# ESPCAT.net
KiCad netlist of a schematic drawn in EAGLE
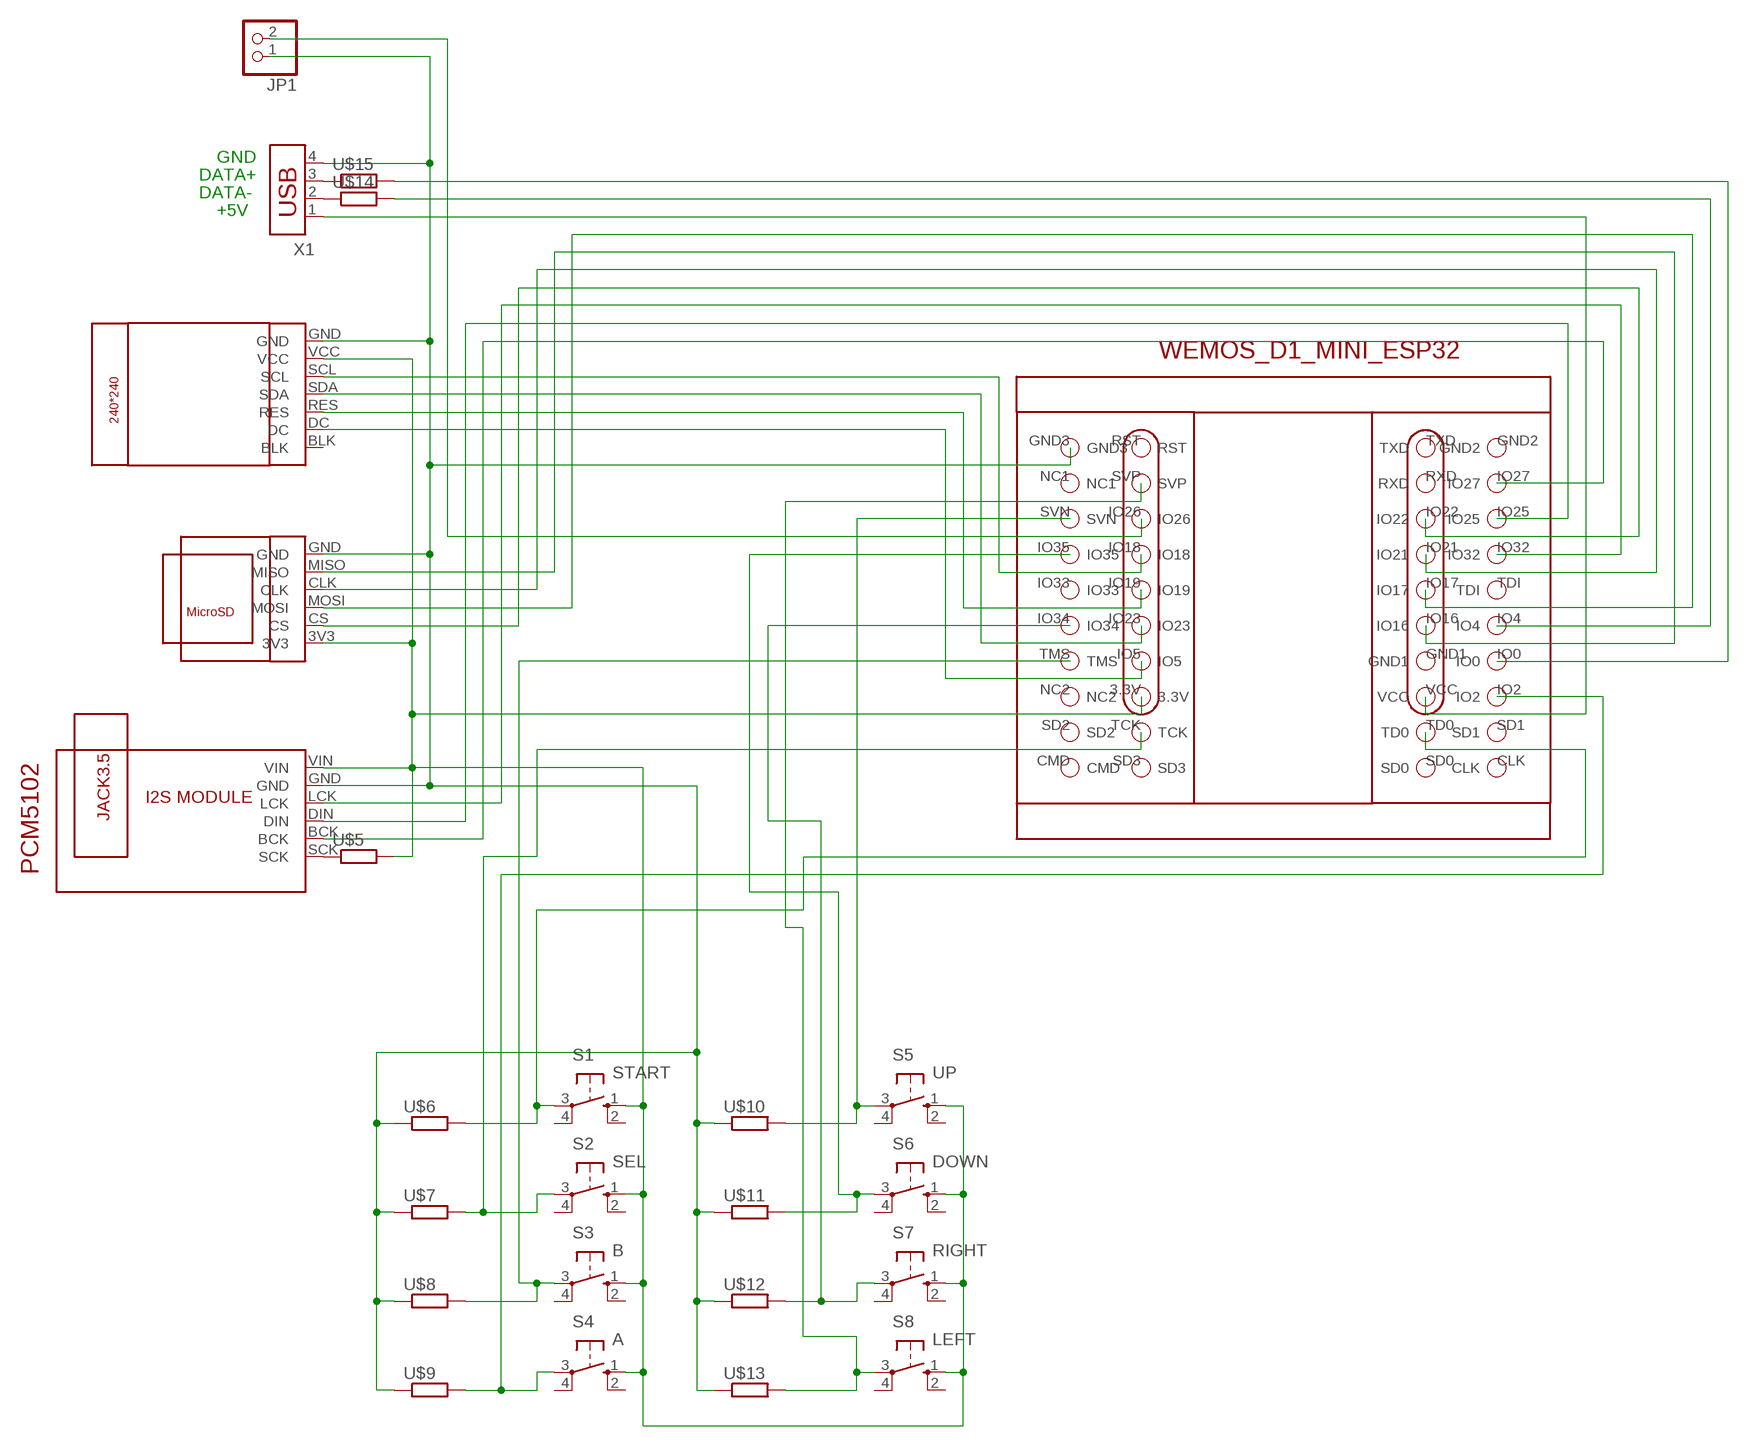
[diagram p0: schematic, sheet 1]

(export (version "E")
  (design (tool "Eeschema 10.0.6"))
  (components
    (comp (ref "JP1")
      (value "PINHD-1X2/90")
      (footprint "eagle-import:1X02_90")
      (libsource (lib "eagle-import") (part "PINHD-1X2/90"))
    )
    (comp (ref "S1")
      (value "START")
      (footprint "eagle-import:B3F-10XX")
      (fields (field (name "MPN") "B3F-1000"))
      (libsource (lib "eagle-import") (part "10-XX"))
    )
    (comp (ref "S2")
      (value "SEL")
      (footprint "eagle-import:B3F-10XX")
      (fields (field (name "MPN") "B3F-1000"))
      (libsource (lib "eagle-import") (part "10-XX"))
    )
    (comp (ref "S3")
      (value "B")
      (footprint "eagle-import:B3F-10XX")
      (fields (field (name "MPN") "B3F-1000"))
      (libsource (lib "eagle-import") (part "10-XX"))
    )
    (comp (ref "S4")
      (value "A")
      (footprint "eagle-import:B3F-10XX")
      (fields (field (name "MPN") "B3F-1000"))
      (libsource (lib "eagle-import") (part "10-XX"))
    )
    (comp (ref "S5")
      (value "UP")
      (footprint "eagle-import:B3F-10XX")
      (fields (field (name "MPN") "B3F-1000"))
      (libsource (lib "eagle-import") (part "10-XX"))
    )
    (comp (ref "S6")
      (value "DOWN")
      (footprint "eagle-import:B3F-10XX")
      (fields (field (name "MPN") "B3F-1000"))
      (libsource (lib "eagle-import") (part "10-XX"))
    )
    (comp (ref "S7")
      (value "RIGHT")
      (footprint "eagle-import:B3F-10XX")
      (fields (field (name "MPN") "B3F-1000"))
      (libsource (lib "eagle-import") (part "10-XX"))
    )
    (comp (ref "S8")
      (value "LEFT")
      (footprint "eagle-import:B3F-10XX")
      (fields (field (name "MPN") "B3F-1000"))
      (libsource (lib "eagle-import") (part "10-XX"))
    )
    (comp (ref "U$1")
      (value "WEMOS_D1_MINI_ESP32")
      (footprint "eagle-import:WEMOS_D1_MINI_ESP32")
      (libsource (lib "eagle-import") (part "WEMOS_D1_MINI_ESP32"))
    )
    (comp (ref "U$2")
      (value "ST7789-1.3INCH")
      (footprint "eagle-import:ST7789-1.3INCH")
      (libsource (lib "eagle-import") (part "ST7789-1.3INCH"))
    )
    (comp (ref "U$3")
      (value "MICROSD-CARD-MODULE")
      (footprint "eagle-import:MICROSD-CARD-MODULE")
      (libsource (lib "eagle-import") (part "MICROSD-CARD-MODULE"))
    )
    (comp (ref "U$4")
      (value "I2S-MODULE-PCM5102A-LITE")
      (footprint "eagle-import:I2S-MODULE-PCM5102A-LITE")
      (libsource (lib "eagle-import") (part "I2S-MODULE-PCM5102A-LITE"))
    )
    (comp (ref "U$5")
      (value "R-RESISTORR-0207/10H")
      (footprint "eagle-import:R-0207_10H")
      (libsource (lib "eagle-import") (part "R-RESISTORR-0207/10H"))
    )
    (comp (ref "U$6")
      (value "R-RESISTORR-0207/10H")
      (footprint "eagle-import:R-0207_10H")
      (libsource (lib "eagle-import") (part "R-RESISTORR-0207/10H"))
    )
    (comp (ref "U$7")
      (value "R-RESISTORR-0207/10H")
      (footprint "eagle-import:R-0207_10H")
      (libsource (lib "eagle-import") (part "R-RESISTORR-0207/10H"))
    )
    (comp (ref "U$8")
      (value "R-RESISTORR-0207/10H")
      (footprint "eagle-import:R-0207_10H")
      (libsource (lib "eagle-import") (part "R-RESISTORR-0207/10H"))
    )
    (comp (ref "U$9")
      (value "R-RESISTORR-0207/10H")
      (footprint "eagle-import:R-0207_10H")
      (libsource (lib "eagle-import") (part "R-RESISTORR-0207/10H"))
    )
    (comp (ref "U$10")
      (value "R-RESISTORR-0207/10H")
      (footprint "eagle-import:R-0207_10H")
      (libsource (lib "eagle-import") (part "R-RESISTORR-0207/10H"))
    )
    (comp (ref "U$11")
      (value "R-RESISTORR-0207/10H")
      (footprint "eagle-import:R-0207_10H")
      (libsource (lib "eagle-import") (part "R-RESISTORR-0207/10H"))
    )
    (comp (ref "U$12")
      (value "R-RESISTORR-0207/10H")
      (footprint "eagle-import:R-0207_10H")
      (libsource (lib "eagle-import") (part "R-RESISTORR-0207/10H"))
    )
    (comp (ref "U$13")
      (value "R-RESISTORR-0207/10H")
      (footprint "eagle-import:R-0207_10H")
      (libsource (lib "eagle-import") (part "R-RESISTORR-0207/10H"))
    )
    (comp (ref "U$14")
      (value "R-RESISTORR-0207/10H")
      (footprint "eagle-import:R-0207_10H")
      (libsource (lib "eagle-import") (part "R-RESISTORR-0207/10H"))
    )
    (comp (ref "U$15")
      (value "R-RESISTORR-0207/10H")
      (footprint "eagle-import:R-0207_10H")
      (libsource (lib "eagle-import") (part "R-RESISTORR-0207/10H"))
    )
    (comp (ref "X1")
      (value "USB-787616")
      (footprint "eagle-import:USB")
      (libsource (lib "eagle-import") (part "USB-787616"))
    )
  )
  (nets
    (net (code "1") (name "Net-(JP1-Pad1)") (class "Default")
      (node (ref "JP1") (pin "1") (pinfunction "1_1") (pintype "passive"))
      (node (ref "U$1") (pin "GND3") (pinfunction "GND3_GND3") (pintype "bidirectional"))
      (node (ref "U$10") (pin "1") (pinfunction "1_1") (pintype "passive"))
      (node (ref "U$11") (pin "1") (pinfunction "1_1") (pintype "passive"))
      (node (ref "U$12") (pin "1") (pinfunction "1_1") (pintype "passive"))
      (node (ref "U$13") (pin "1") (pinfunction "1_1") (pintype "passive"))
      (node (ref "U$2") (pin "GND") (pinfunction "GND_GND") (pintype "bidirectional"))
      (node (ref "U$3") (pin "GND") (pinfunction "GND_GND") (pintype "bidirectional"))
      (node (ref "U$4") (pin "GND") (pinfunction "GND_GND") (pintype "bidirectional"))
      (node (ref "U$6") (pin "1") (pinfunction "1_1") (pintype "passive"))
      (node (ref "U$7") (pin "1") (pinfunction "1_1") (pintype "passive"))
      (node (ref "U$8") (pin "1") (pinfunction "1_1") (pintype "passive"))
      (node (ref "U$9") (pin "1") (pinfunction "1_1") (pintype "passive"))
      (node (ref "X1") (pin "4") (pinfunction "4_4") (pintype "passive"))
    )
    (net (code "2") (name "Net-(JP1-Pad2)") (class "Default")
      (node (ref "JP1") (pin "2") (pinfunction "2_2") (pintype "passive"))
      (node (ref "U$1") (pin "IO26") (pinfunction "IO26_IO26") (pintype "bidirectional"))
    )
    (net (code "3") (name "Net-(S1-P)") (class "Default")
      (node (ref "S1") (pin "3") (pinfunction "P_3") (pintype "passive"))
      (node (ref "U$1") (pin "TD0") (pinfunction "TD0_TD0") (pintype "bidirectional"))
      (node (ref "U$6") (pin "2") (pinfunction "2_2") (pintype "passive"))
    )
    (net (code "4") (name "Net-(S1-S)") (class "Default")
      (node (ref "S1") (pin "1") (pinfunction "S_1") (pintype "passive"))
      (node (ref "S2") (pin "1") (pinfunction "S_1") (pintype "passive"))
      (node (ref "S3") (pin "1") (pinfunction "S_1") (pintype "passive"))
      (node (ref "S4") (pin "1") (pinfunction "S_1") (pintype "passive"))
      (node (ref "S5") (pin "1") (pinfunction "S_1") (pintype "passive"))
      (node (ref "S6") (pin "1") (pinfunction "S_1") (pintype "passive"))
      (node (ref "S7") (pin "1") (pinfunction "S_1") (pintype "passive"))
      (node (ref "S8") (pin "1") (pinfunction "S_1") (pintype "passive"))
      (node (ref "U$1") (pin "3.3V") (pinfunction "3.3V_3.3V") (pintype "bidirectional"))
      (node (ref "U$2") (pin "VCC") (pinfunction "VCC_VCC") (pintype "bidirectional"))
      (node (ref "U$3") (pin "3V3") (pinfunction "3V3_3V3") (pintype "bidirectional"))
      (node (ref "U$4") (pin "VIN") (pinfunction "VIN_VIN") (pintype "bidirectional"))
      (node (ref "U$5") (pin "2") (pinfunction "2_2") (pintype "passive"))
    )
    (net (code "5") (name "Net-(S2-P)") (class "Default")
      (node (ref "S2") (pin "3") (pinfunction "P_3") (pintype "passive"))
      (node (ref "U$1") (pin "TCK") (pinfunction "TCK_TCK") (pintype "bidirectional"))
      (node (ref "U$7") (pin "2") (pinfunction "2_2") (pintype "passive"))
    )
    (net (code "6") (name "Net-(S3-P)") (class "Default")
      (node (ref "S3") (pin "3") (pinfunction "P_3") (pintype "passive"))
      (node (ref "U$1") (pin "TMS") (pinfunction "TMS_TMS") (pintype "bidirectional"))
      (node (ref "U$8") (pin "2") (pinfunction "2_2") (pintype "passive"))
    )
    (net (code "7") (name "Net-(S4-P)") (class "Default")
      (node (ref "S4") (pin "3") (pinfunction "P_3") (pintype "passive"))
      (node (ref "U$1") (pin "IO2") (pinfunction "IO2_IO2") (pintype "bidirectional"))
      (node (ref "U$9") (pin "2") (pinfunction "2_2") (pintype "passive"))
    )
    (net (code "8") (name "Net-(S5-P)") (class "Default")
      (node (ref "S5") (pin "3") (pinfunction "P_3") (pintype "passive"))
      (node (ref "U$1") (pin "SVN") (pinfunction "SVN_SVN") (pintype "bidirectional"))
      (node (ref "U$10") (pin "2") (pinfunction "2_2") (pintype "passive"))
    )
    (net (code "9") (name "Net-(S6-P)") (class "Default")
      (node (ref "S6") (pin "3") (pinfunction "P_3") (pintype "passive"))
      (node (ref "U$1") (pin "IO35") (pinfunction "IO35_IO35") (pintype "bidirectional"))
      (node (ref "U$11") (pin "2") (pinfunction "2_2") (pintype "passive"))
    )
    (net (code "10") (name "Net-(S7-P)") (class "Default")
      (node (ref "S7") (pin "3") (pinfunction "P_3") (pintype "passive"))
      (node (ref "U$1") (pin "IO34") (pinfunction "IO34_IO34") (pintype "bidirectional"))
      (node (ref "U$12") (pin "2") (pinfunction "2_2") (pintype "passive"))
    )
    (net (code "11") (name "Net-(S8-P)") (class "Default")
      (node (ref "S8") (pin "3") (pinfunction "P_3") (pintype "passive"))
      (node (ref "U$1") (pin "SVP") (pinfunction "SVP_SVP") (pintype "bidirectional"))
      (node (ref "U$13") (pin "2") (pinfunction "2_2") (pintype "passive"))
    )
    (net (code "12") (name "Net-(U$1-PadIO0)") (class "Default")
      (node (ref "U$1") (pin "IO0") (pinfunction "IO0_IO0") (pintype "bidirectional"))
      (node (ref "U$15") (pin "2") (pinfunction "2_2") (pintype "passive"))
    )
    (net (code "13") (name "Net-(U$1-PadIO4)") (class "Default")
      (node (ref "U$1") (pin "IO4") (pinfunction "IO4_IO4") (pintype "bidirectional"))
      (node (ref "U$14") (pin "2") (pinfunction "2_2") (pintype "passive"))
    )
    (net (code "14") (name "Net-(U$1-PadIO5)") (class "Default")
      (node (ref "U$1") (pin "IO5") (pinfunction "IO5_IO5") (pintype "bidirectional"))
      (node (ref "U$2") (pin "DC") (pinfunction "DC_DC") (pintype "bidirectional"))
    )
    (net (code "15") (name "Net-(U$1-PadIO16)") (class "Default")
      (node (ref "U$1") (pin "IO16") (pinfunction "IO16_IO16") (pintype "bidirectional"))
      (node (ref "U$3") (pin "MISO") (pinfunction "MISO_MISO") (pintype "bidirectional"))
    )
    (net (code "16") (name "Net-(U$1-PadIO17)") (class "Default")
      (node (ref "U$1") (pin "IO17") (pinfunction "IO17_IO17") (pintype "bidirectional"))
      (node (ref "U$3") (pin "MOSI") (pinfunction "MOSI_MOSI") (pintype "bidirectional"))
    )
    (net (code "17") (name "Net-(U$1-PadIO18)") (class "Default")
      (node (ref "U$1") (pin "IO18") (pinfunction "IO18_IO18") (pintype "bidirectional"))
      (node (ref "U$2") (pin "SCL") (pinfunction "SCL_SCL") (pintype "bidirectional"))
    )
    (net (code "18") (name "Net-(U$1-PadIO19)") (class "Default")
      (node (ref "U$1") (pin "IO19") (pinfunction "IO19_IO19") (pintype "bidirectional"))
      (node (ref "U$2") (pin "RES") (pinfunction "RES_RES") (pintype "bidirectional"))
    )
    (net (code "19") (name "Net-(U$1-PadIO21)") (class "Default")
      (node (ref "U$1") (pin "IO21") (pinfunction "IO21_IO21") (pintype "bidirectional"))
      (node (ref "U$3") (pin "CLK") (pinfunction "CLK_CLK") (pintype "bidirectional"))
    )
    (net (code "20") (name "Net-(U$1-PadIO22)") (class "Default")
      (node (ref "U$1") (pin "IO22") (pinfunction "IO22_IO22") (pintype "bidirectional"))
      (node (ref "U$3") (pin "CS") (pinfunction "CS_CS") (pintype "bidirectional"))
    )
    (net (code "21") (name "Net-(U$1-PadIO23)") (class "Default")
      (node (ref "U$1") (pin "IO23") (pinfunction "IO23_IO23") (pintype "bidirectional"))
      (node (ref "U$2") (pin "SDA") (pinfunction "SDA_SDA") (pintype "bidirectional"))
    )
    (net (code "22") (name "Net-(U$1-PadIO25)") (class "Default")
      (node (ref "U$1") (pin "IO25") (pinfunction "IO25_IO25") (pintype "bidirectional"))
      (node (ref "U$4") (pin "DIN") (pinfunction "DIN_DIN") (pintype "bidirectional"))
    )
    (net (code "23") (name "Net-(U$1-PadIO27)") (class "Default")
      (node (ref "U$1") (pin "IO27") (pinfunction "IO27_IO27") (pintype "bidirectional"))
      (node (ref "U$4") (pin "BCK") (pinfunction "BCK_BCK") (pintype "bidirectional"))
    )
    (net (code "24") (name "Net-(U$1-PadIO32)") (class "Default")
      (node (ref "U$1") (pin "IO32") (pinfunction "IO32_IO32") (pintype "bidirectional"))
      (node (ref "U$4") (pin "LCK") (pinfunction "LCK_LCK") (pintype "bidirectional"))
    )
    (net (code "25") (name "Net-(U$1-PadVCC)") (class "Default")
      (node (ref "U$1") (pin "VCC") (pinfunction "VCC_VCC") (pintype "bidirectional"))
      (node (ref "X1") (pin "1") (pinfunction "1_1") (pintype "passive"))
    )
    (net (code "26") (name "Net-(U$4-PadSCK)") (class "Default")
      (node (ref "U$4") (pin "SCK") (pinfunction "SCK_SCK") (pintype "bidirectional"))
      (node (ref "U$5") (pin "1") (pinfunction "1_1") (pintype "passive"))
    )
    (net (code "27") (name "Net-(U$14-Pad1)") (class "Default")
      (node (ref "U$14") (pin "1") (pinfunction "1_1") (pintype "passive"))
      (node (ref "X1") (pin "2") (pinfunction "2_2") (pintype "passive"))
    )
    (net (code "28") (name "Net-(U$15-Pad1)") (class "Default")
      (node (ref "U$15") (pin "1") (pinfunction "1_1") (pintype "passive"))
      (node (ref "X1") (pin "3") (pinfunction "3_3") (pintype "passive"))
    )
    (net (code "29") (name "unconnected-(S1-P1-Pad4)") (class "Default")
      (node (ref "S1") (pin "4") (pinfunction "P1_4") (pintype "passive"))
    )
    (net (code "30") (name "unconnected-(S1-S1-Pad2)") (class "Default")
      (node (ref "S1") (pin "2") (pinfunction "S1_2") (pintype "passive"))
    )
    (net (code "31") (name "unconnected-(S2-P1-Pad4)") (class "Default")
      (node (ref "S2") (pin "4") (pinfunction "P1_4") (pintype "passive"))
    )
    (net (code "32") (name "unconnected-(S2-S1-Pad2)") (class "Default")
      (node (ref "S2") (pin "2") (pinfunction "S1_2") (pintype "passive"))
    )
    (net (code "33") (name "unconnected-(S3-P1-Pad4)") (class "Default")
      (node (ref "S3") (pin "4") (pinfunction "P1_4") (pintype "passive"))
    )
    (net (code "34") (name "unconnected-(S3-S1-Pad2)") (class "Default")
      (node (ref "S3") (pin "2") (pinfunction "S1_2") (pintype "passive"))
    )
    (net (code "35") (name "unconnected-(S4-P1-Pad4)") (class "Default")
      (node (ref "S4") (pin "4") (pinfunction "P1_4") (pintype "passive"))
    )
    (net (code "36") (name "unconnected-(S4-S1-Pad2)") (class "Default")
      (node (ref "S4") (pin "2") (pinfunction "S1_2") (pintype "passive"))
    )
    (net (code "37") (name "unconnected-(S5-P1-Pad4)") (class "Default")
      (node (ref "S5") (pin "4") (pinfunction "P1_4") (pintype "passive"))
    )
    (net (code "38") (name "unconnected-(S5-S1-Pad2)") (class "Default")
      (node (ref "S5") (pin "2") (pinfunction "S1_2") (pintype "passive"))
    )
    (net (code "39") (name "unconnected-(S6-P1-Pad4)") (class "Default")
      (node (ref "S6") (pin "4") (pinfunction "P1_4") (pintype "passive"))
    )
    (net (code "40") (name "unconnected-(S6-S1-Pad2)") (class "Default")
      (node (ref "S6") (pin "2") (pinfunction "S1_2") (pintype "passive"))
    )
    (net (code "41") (name "unconnected-(S7-P1-Pad4)") (class "Default")
      (node (ref "S7") (pin "4") (pinfunction "P1_4") (pintype "passive"))
    )
    (net (code "42") (name "unconnected-(S7-S1-Pad2)") (class "Default")
      (node (ref "S7") (pin "2") (pinfunction "S1_2") (pintype "passive"))
    )
    (net (code "43") (name "unconnected-(S8-P1-Pad4)") (class "Default")
      (node (ref "S8") (pin "4") (pinfunction "P1_4") (pintype "passive"))
    )
    (net (code "44") (name "unconnected-(S8-S1-Pad2)") (class "Default")
      (node (ref "S8") (pin "2") (pinfunction "S1_2") (pintype "passive"))
    )
    (net (code "45") (name "unconnected-(U$1-PadCLK)") (class "Default")
      (node (ref "U$1") (pin "CLK") (pinfunction "CLK_CLK") (pintype "bidirectional"))
    )
    (net (code "46") (name "unconnected-(U$1-PadCMD)") (class "Default")
      (node (ref "U$1") (pin "CMD") (pinfunction "CMD_CMD") (pintype "bidirectional"))
    )
    (net (code "47") (name "unconnected-(U$1-PadGND1)") (class "Default")
      (node (ref "U$1") (pin "GND1") (pinfunction "GND1_GND1") (pintype "bidirectional"))
    )
    (net (code "48") (name "unconnected-(U$1-PadGND2)") (class "Default")
      (node (ref "U$1") (pin "GND2") (pinfunction "GND2_GND2") (pintype "bidirectional"))
    )
    (net (code "49") (name "unconnected-(U$1-PadIO33)") (class "Default")
      (node (ref "U$1") (pin "IO33") (pinfunction "IO33_IO33") (pintype "bidirectional"))
    )
    (net (code "50") (name "unconnected-(U$1-PadNC1)") (class "Default")
      (node (ref "U$1") (pin "NC1") (pinfunction "NC1_NC1") (pintype "bidirectional"))
    )
    (net (code "51") (name "unconnected-(U$1-PadNC2)") (class "Default")
      (node (ref "U$1") (pin "NC2") (pinfunction "NC2_NC2") (pintype "bidirectional"))
    )
    (net (code "52") (name "unconnected-(U$1-PadRST)") (class "Default")
      (node (ref "U$1") (pin "RST") (pinfunction "RST_RST") (pintype "bidirectional"))
    )
    (net (code "53") (name "unconnected-(U$1-PadRXD)") (class "Default")
      (node (ref "U$1") (pin "RXD") (pinfunction "RXD_RXD") (pintype "bidirectional"))
    )
    (net (code "54") (name "unconnected-(U$1-PadSD0)") (class "Default")
      (node (ref "U$1") (pin "SD0") (pinfunction "SD0_SD0") (pintype "bidirectional"))
    )
    (net (code "55") (name "unconnected-(U$1-PadSD1)") (class "Default")
      (node (ref "U$1") (pin "SD1") (pinfunction "SD1_SD1") (pintype "bidirectional"))
    )
    (net (code "56") (name "unconnected-(U$1-PadSD2)") (class "Default")
      (node (ref "U$1") (pin "SD2") (pinfunction "SD2_SD2") (pintype "bidirectional"))
    )
    (net (code "57") (name "unconnected-(U$1-PadSD3)") (class "Default")
      (node (ref "U$1") (pin "SD3") (pinfunction "SD3_SD3") (pintype "bidirectional"))
    )
    (net (code "58") (name "unconnected-(U$1-PadTDI)") (class "Default")
      (node (ref "U$1") (pin "TDI") (pinfunction "TDI_TDI") (pintype "bidirectional"))
    )
    (net (code "59") (name "unconnected-(U$1-PadTXD)") (class "Default")
      (node (ref "U$1") (pin "TXD") (pinfunction "TXD_TXD") (pintype "bidirectional"))
    )
    (net (code "60") (name "unconnected-(U$2-PadBLK)") (class "Default")
      (node (ref "U$2") (pin "BLK") (pinfunction "BLK_BLK") (pintype "bidirectional"))
    )
  )
)
